# DCDCDC-R2.net
KiCad netlist of a schematic drawn in EAGLE
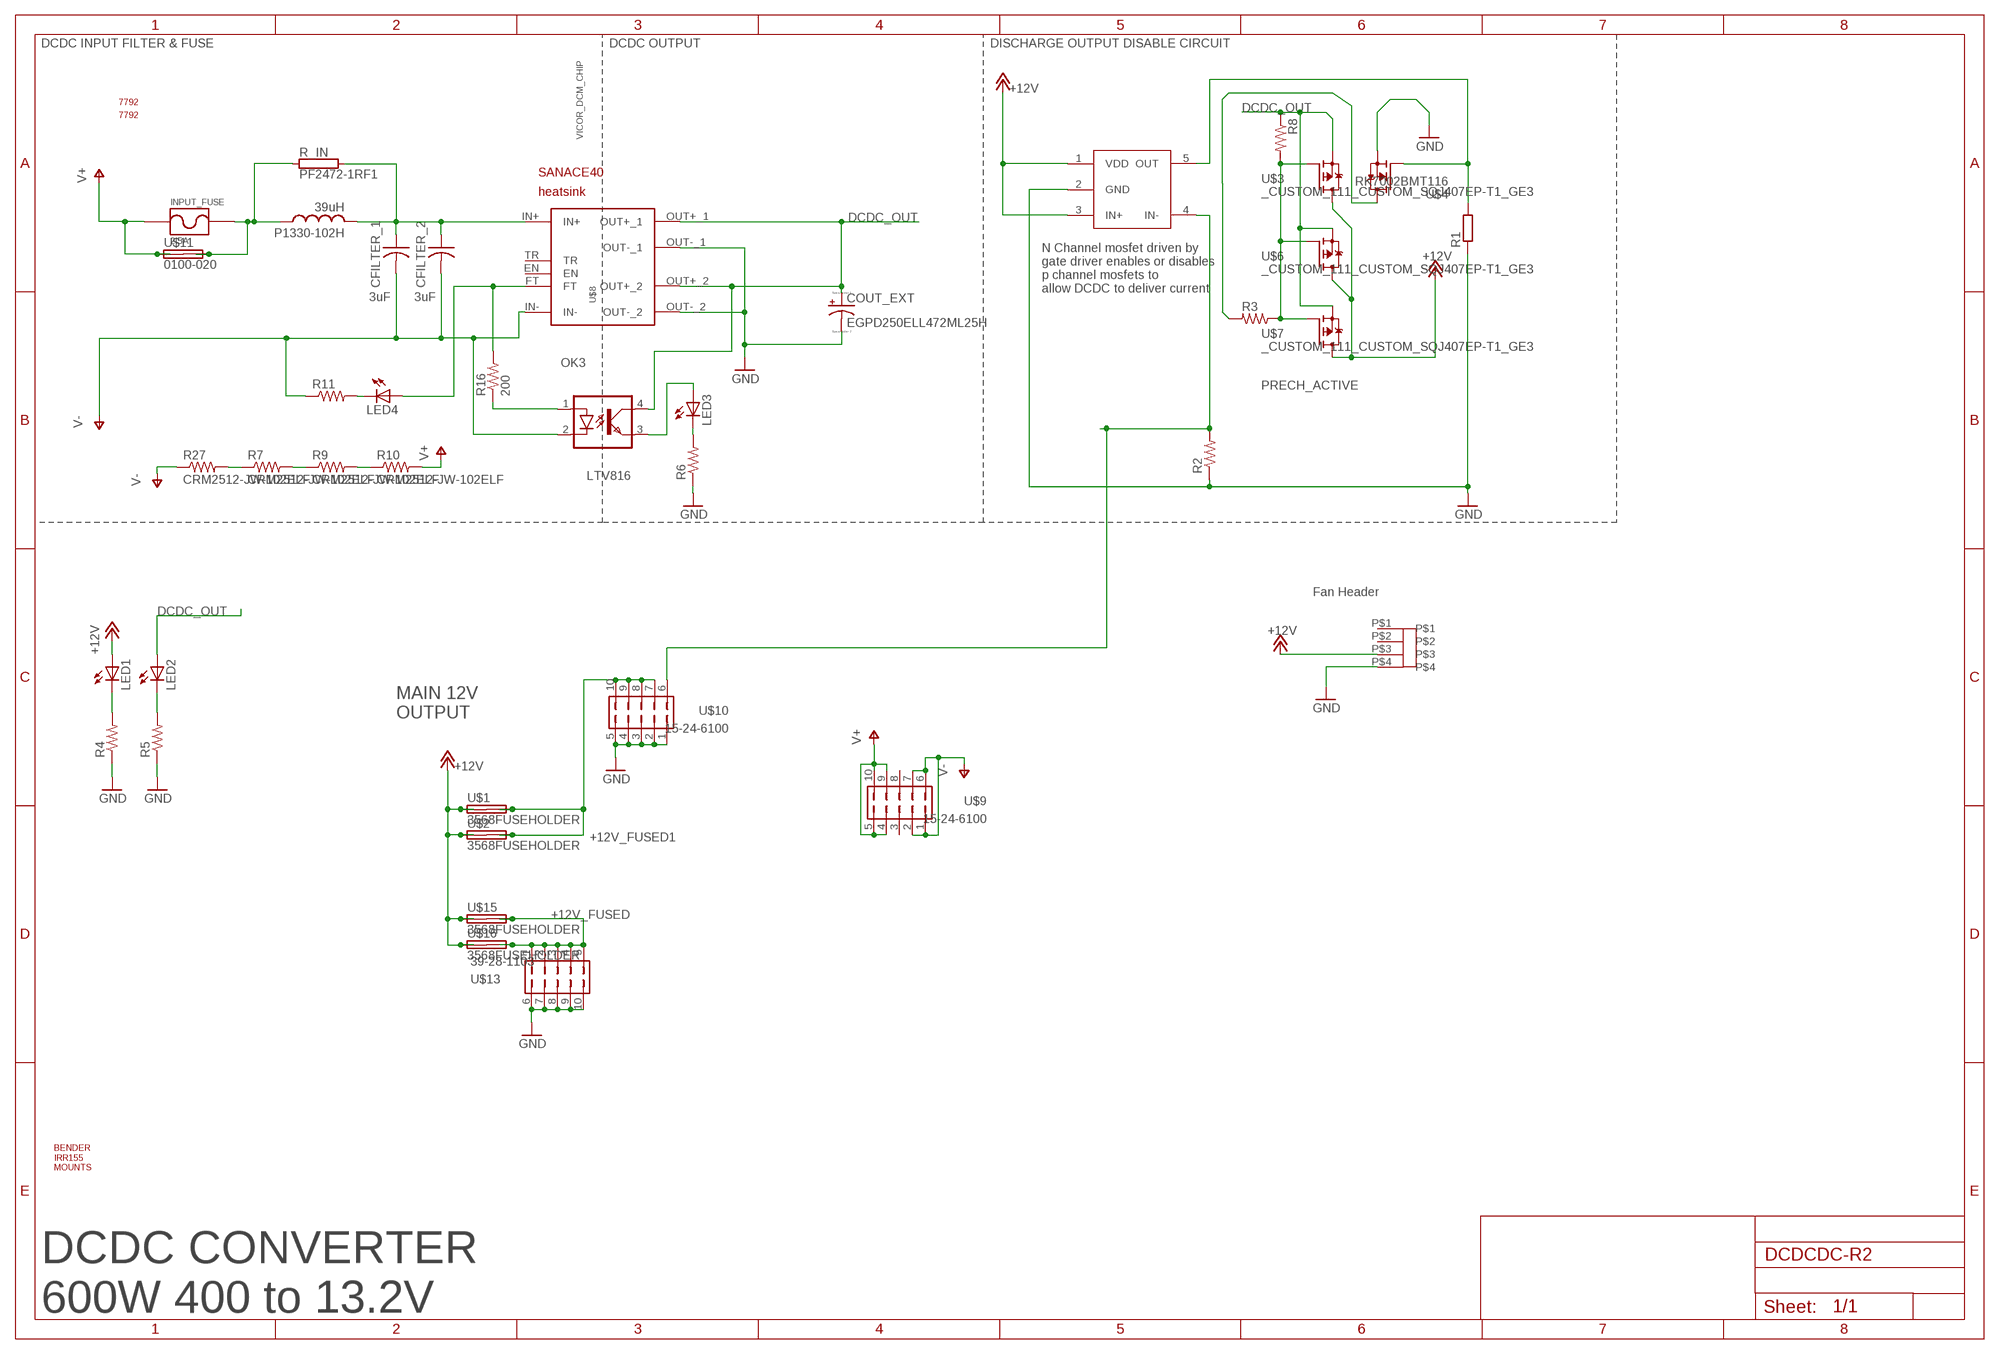
[diagram p0: schematic, sheet 1]

(export (version "E")
  (design (tool "Eeschema 10.0.6"))
  (components
    (comp (ref "CFILTER_1")
      (value "3uF")
      (footprint "eagle-import:CERALINK_FA3")
      (libsource (lib "eagle-import") (part "B58035U5305M062"))
    )
    (comp (ref "CFILTER_2")
      (value "3uF")
      (footprint "eagle-import:CERALINK_FA3")
      (libsource (lib "eagle-import") (part "B58035U5305M062"))
    )
    (comp (ref "COUT_EXT")
      (value "EGPD250ELL472ML25H")
      (footprint "eagle-import:E7,5-16")
      (libsource (lib "eagle-import") (part "CPOL-USE7.5-16"))
    )
    (comp (ref "INPUT_FUSE")
      (value "2.5A")
      (footprint "eagle-import:_CUSTOM_PARTS_LF_885")
      (libsource (lib "eagle-import") (part "_CUSTOM_PARTS_LF_885"))
    )
    (comp (ref "LED1")
      (value "LEDCHIPLED_0805")
      (footprint "eagle-import:CHIPLED_0805")
      (libsource (lib "eagle-import") (part "LEDCHIPLED_0805"))
    )
    (comp (ref "LED2")
      (value "LEDCHIPLED_0805")
      (footprint "eagle-import:CHIPLED_0805")
      (libsource (lib "eagle-import") (part "LEDCHIPLED_0805"))
    )
    (comp (ref "LED3")
      (value "LEDCHIPLED_0805")
      (footprint "eagle-import:CHIPLED_0805")
      (libsource (lib "eagle-import") (part "LEDCHIPLED_0805"))
    )
    (comp (ref "LED4")
      (value "LEDCHIPLED_0805")
      (footprint "eagle-import:CHIPLED_0805")
      (libsource (lib "eagle-import") (part "LEDCHIPLED_0805"))
    )
    (comp (ref "OK3")
      (value "LTV816")
      (footprint "eagle-import:DIL04")
      (libsource (lib "eagle-import") (part "LTV816"))
    )
    (comp (ref "P1330-102H")
      (value "39uH")
      (footprint "eagle-import:L_1510_NONSTANDARD")
      (libsource (lib "eagle-import") (part "SRP1770TA-390M"))
    )
    (comp (ref "R1")
      (value "R-EU_R0805")
      (footprint "eagle-import:R0805")
      (libsource (lib "eagle-import") (part "R-EU_R0805"))
    )
    (comp (ref "R2")
      (value "R-US_R0805")
      (footprint "eagle-import:R0805")
      (libsource (lib "eagle-import") (part "ACC-MB-R0_13324935_R-US_R0805"))
    )
    (comp (ref "R3")
      (value "R-US_R0805")
      (footprint "eagle-import:R0805")
      (libsource (lib "eagle-import") (part "ACC-MB-R0_13324935_R-US_R0805"))
    )
    (comp (ref "R4")
      (value "R-US_R0805")
      (footprint "eagle-import:R0805")
      (libsource (lib "eagle-import") (part "R-US_R0805"))
    )
    (comp (ref "R5")
      (value "R-US_R0805")
      (footprint "eagle-import:R0805")
      (libsource (lib "eagle-import") (part "R-US_R0805"))
    )
    (comp (ref "R6")
      (value "R-US_R0805")
      (footprint "eagle-import:R0805")
      (libsource (lib "eagle-import") (part "R-US_R0805"))
    )
    (comp (ref "R7")
      (value "CRM2512-JW-102ELF")
      (footprint "eagle-import:R2512")
      (libsource (lib "eagle-import") (part "R-US_R2512"))
    )
    (comp (ref "R8")
      (value "R-US_R0805")
      (footprint "eagle-import:R0805")
      (libsource (lib "eagle-import") (part "ACC-MB-R0_13324935_R-US_R0805"))
    )
    (comp (ref "R9")
      (value "CRM2512-JW-102ELF")
      (footprint "eagle-import:R2512")
      (libsource (lib "eagle-import") (part "R-US_R2512"))
    )
    (comp (ref "R10")
      (value "CRM2512-JW-102ELF")
      (footprint "eagle-import:R2512")
      (libsource (lib "eagle-import") (part "R-US_R2512"))
    )
    (comp (ref "R11")
      (value "R-US_R0805")
      (footprint "eagle-import:R0805")
      (libsource (lib "eagle-import") (part "R-US_R0805"))
    )
    (comp (ref "R16")
      (value "200")
      (footprint "eagle-import:R2010")
      (libsource (lib "eagle-import") (part "Main_14107900_R-US_R2010"))
    )
    (comp (ref "R27")
      (value "CRM2512-JW-102ELF")
      (footprint "eagle-import:R2512")
      (libsource (lib "eagle-import") (part "R-US_R2512"))
    )
    (comp (ref "R_IN")
      (value "PF2472-1RF1")
      (footprint "eagle-import:TO-247-2V")
      (libsource (lib "eagle-import") (part "RMG100-V"))
    )
    (comp (ref "U$1")
      (value "3568FUSEHOLDER")
      (footprint "eagle-import:3568")
      (libsource (lib "eagle-import") (part "3568FUSEHOLDER"))
    )
    (comp (ref "U$2")
      (value "3568FUSEHOLDER")
      (footprint "eagle-import:3568")
      (libsource (lib "eagle-import") (part "3568FUSEHOLDER"))
    )
    (comp (ref "U$3")
      (value "_CUSTOM_111_CUSTOM_SQJ407EP-T1_GE3")
      (footprint "eagle-import:_CUSTOM_111_CUSTOM_TRANS_SIRA90DP-T1-GE3")
      (libsource (lib "eagle-import") (part "_CUSTOM_111_CUSTOM_SQJ407EP-T1_GE3"))
    )
    (comp (ref "U$4")
      (value "RK7002BMT116")
      (footprint "eagle-import:SOT23")
      (libsource (lib "eagle-import") (part "RK7002BMT116"))
    )
    (comp (ref "U$5")
      (value "UCC27511AQDBVRQ1")
      (footprint "eagle-import:SOT23-5L")
      (libsource (lib "eagle-import") (part "UCC27511AQDBVRQ1"))
    )
    (comp (ref "U$6")
      (value "_CUSTOM_111_CUSTOM_SQJ407EP-T1_GE3")
      (footprint "eagle-import:_CUSTOM_111_CUSTOM_TRANS_SIRA90DP-T1-GE3")
      (libsource (lib "eagle-import") (part "_CUSTOM_111_CUSTOM_SQJ407EP-T1_GE3"))
    )
    (comp (ref "U$7")
      (value "_CUSTOM_111_CUSTOM_SQJ407EP-T1_GE3")
      (footprint "eagle-import:_CUSTOM_111_CUSTOM_TRANS_SIRA90DP-T1-GE3")
      (libsource (lib "eagle-import") (part "_CUSTOM_111_CUSTOM_SQJ407EP-T1_GE3"))
    )
    (comp (ref "U$8")
      (value "VICOR_DCM_CHIP")
      (footprint "eagle-import:VICOR_CHIP_HEATSINK")
      (libsource (lib "eagle-import") (part "VICOR_DCM_CHIP"))
    )
    (comp (ref "U$9")
      (value "15-24-6100")
      (footprint "eagle-import:15-24-6100")
      (libsource (lib "eagle-import") (part "15-24-6100"))
    )
    (comp (ref "U$10")
      (value "15-24-6100")
      (footprint "eagle-import:15-24-6100")
      (libsource (lib "eagle-import") (part "15-24-6100"))
    )
    (comp (ref "U$11")
      (value "0100-020")
      (footprint "eagle-import:0100-020")
      (libsource (lib "eagle-import") (part "0100-020"))
    )
    (comp (ref "U$12")
      (value "VICOR_HEATSINK_DOUBLE")
      (footprint "eagle-import:VICOR_HEATSINK_DOUBLE")
      (libsource (lib "eagle-import") (part "VICOR_HEATSINK_DOUBLE"))
    )
    (comp (ref "U$13")
      (value "39-28-1103")
      (footprint "eagle-import:39-28-1103")
      (libsource (lib "eagle-import") (part "39-28-1103"))
    )
    (comp (ref "U$14")
      (value "7792")
      (footprint "eagle-import:7792")
      (libsource (lib "eagle-import") (part "7792"))
    )
    (comp (ref "U$15")
      (value "3568FUSEHOLDER")
      (footprint "eagle-import:3568")
      (libsource (lib "eagle-import") (part "3568FUSEHOLDER"))
    )
    (comp (ref "U$16")
      (value "3568FUSEHOLDER")
      (footprint "eagle-import:3568")
      (libsource (lib "eagle-import") (part "3568FUSEHOLDER"))
    )
    (comp (ref "U$17")
      (value "7792")
      (footprint "eagle-import:7792")
      (libsource (lib "eagle-import") (part "7792"))
    )
    (comp (ref "U$18")
      (value "9GAX0412P3S0031")
      (footprint "eagle-import:SANACE40")
      (libsource (lib "eagle-import") (part "SANACE40"))
    )
    (comp (ref "U$19")
      (value "470531000")
      (footprint "eagle-import:470531000")
      (libsource (lib "eagle-import") (part "470531000"))
    )
    (comp (ref "U$20")
      (value "BENDER_IRR155")
      (footprint "eagle-import:BENDER_IRR155")
      (libsource (lib "eagle-import") (part "BENDER_IRR155"))
    )
  )
  (nets
    (net (code "1") (name "+12V") (class "Default")
      (node (ref "LED1") (pin "A") (pinfunction "A_A") (pintype "passive"))
      (node (ref "U$1") (pin "L1") (pinfunction "1A_L1") (pintype "passive"))
      (node (ref "U$1") (pin "L2") (pinfunction "1B_L2") (pintype "passive"))
      (node (ref "U$15") (pin "L1") (pinfunction "1A_L1") (pintype "passive"))
      (node (ref "U$15") (pin "L2") (pinfunction "1B_L2") (pintype "passive"))
      (node (ref "U$16") (pin "L1") (pinfunction "1A_L1") (pintype "passive"))
      (node (ref "U$16") (pin "L2") (pinfunction "1B_L2") (pintype "passive"))
      (node (ref "U$19") (pin "P$3") (pinfunction "P$3_P$3") (pintype "bidirectional"))
      (node (ref "U$2") (pin "L1") (pinfunction "1A_L1") (pintype "passive"))
      (node (ref "U$2") (pin "L2") (pinfunction "1B_L2") (pintype "passive"))
      (node (ref "U$3") (pin "5") (pinfunction "D_5") (pintype "passive"))
      (node (ref "U$5") (pin "1") (pinfunction "VDD_1") (pintype "bidirectional"))
      (node (ref "U$5") (pin "3") (pinfunction "IN+_3") (pintype "bidirectional"))
      (node (ref "U$6") (pin "5") (pinfunction "D_5") (pintype "passive"))
      (node (ref "U$7") (pin "5") (pinfunction "D_5") (pintype "passive"))
    )
    (net (code "2") (name "/+12V_FUSED") (class "Default")
      (node (ref "U$13") (pin "1") (pinfunction "1_1") (pintype "passive"))
      (node (ref "U$13") (pin "2") (pinfunction "2_2") (pintype "passive"))
      (node (ref "U$13") (pin "3") (pinfunction "3_3") (pintype "passive"))
      (node (ref "U$13") (pin "4") (pinfunction "4_4") (pintype "passive"))
      (node (ref "U$13") (pin "5") (pinfunction "5_5") (pintype "passive"))
      (node (ref "U$15") (pin "R1") (pinfunction "2A_R1") (pintype "passive"))
      (node (ref "U$15") (pin "R2") (pinfunction "2B_R2") (pintype "passive"))
      (node (ref "U$16") (pin "R1") (pinfunction "2A_R1") (pintype "passive"))
      (node (ref "U$16") (pin "R2") (pinfunction "2B_R2") (pintype "passive"))
    )
    (net (code "3") (name "/+12V_FUSED1") (class "Default")
      (node (ref "U$1") (pin "R1") (pinfunction "2A_R1") (pintype "passive"))
      (node (ref "U$1") (pin "R2") (pinfunction "2B_R2") (pintype "passive"))
      (node (ref "U$10") (pin "10") (pinfunction "10_10") (pintype "passive"))
      (node (ref "U$10") (pin "7") (pinfunction "7_7") (pintype "passive"))
      (node (ref "U$10") (pin "8") (pinfunction "8_8") (pintype "passive"))
      (node (ref "U$10") (pin "9") (pinfunction "9_9") (pintype "passive"))
      (node (ref "U$2") (pin "R1") (pinfunction "2A_R1") (pintype "passive"))
      (node (ref "U$2") (pin "R2") (pinfunction "2B_R2") (pintype "passive"))
    )
    (net (code "4") (name "/DCDC_OUT") (class "Default")
      (node (ref "COUT_EXT") (pin "+") (pinfunction "+_+") (pintype "passive"))
      (node (ref "LED2") (pin "A") (pinfunction "A_A") (pintype "passive"))
      (node (ref "OK3") (pin "4") (pinfunction "COL_4") (pintype "passive"))
      (node (ref "R8") (pin "1") (pinfunction "1_1") (pintype "passive"))
      (node (ref "U$3") (pin "1") (pinfunction "S_1") (pintype "passive"))
      (node (ref "U$3") (pin "2") (pinfunction "S_2") (pintype "passive"))
      (node (ref "U$3") (pin "3") (pinfunction "S_3") (pintype "passive"))
      (node (ref "U$6") (pin "1") (pinfunction "S_1") (pintype "passive"))
      (node (ref "U$6") (pin "2") (pinfunction "S_2") (pintype "passive"))
      (node (ref "U$6") (pin "3") (pinfunction "S_3") (pintype "passive"))
      (node (ref "U$7") (pin "1") (pinfunction "S_1") (pintype "passive"))
      (node (ref "U$7") (pin "2") (pinfunction "S_2") (pintype "passive"))
      (node (ref "U$7") (pin "3") (pinfunction "S_3") (pintype "passive"))
      (node (ref "U$8") (pin "OUT+_1") (pinfunction "OUT+_1_OUT+_1") (pintype "bidirectional"))
      (node (ref "U$8") (pin "OUT+_2") (pinfunction "OUT+_2_OUT+_2") (pintype "bidirectional"))
    )
    (net (code "5") (name "/PRECH_ACTIVE") (class "Default")
      (node (ref "R2") (pin "2") (pinfunction "2_2") (pintype "passive"))
      (node (ref "U$10") (pin "6") (pinfunction "6_6") (pintype "passive"))
      (node (ref "U$5") (pin "4") (pinfunction "IN-_4") (pintype "bidirectional"))
    )
    (net (code "6") (name "GND") (class "Default")
      (node (ref "COUT_EXT") (pin "-") (pinfunction "-_-") (pintype "passive"))
      (node (ref "R1") (pin "1") (pinfunction "1_1") (pintype "passive"))
      (node (ref "R2") (pin "1") (pinfunction "1_1") (pintype "passive"))
      (node (ref "R4") (pin "1") (pinfunction "1_1") (pintype "passive"))
      (node (ref "R5") (pin "1") (pinfunction "1_1") (pintype "passive"))
      (node (ref "R6") (pin "1") (pinfunction "1_1") (pintype "passive"))
      (node (ref "U$10") (pin "1") (pinfunction "1_1") (pintype "passive"))
      (node (ref "U$10") (pin "2") (pinfunction "2_2") (pintype "passive"))
      (node (ref "U$10") (pin "3") (pinfunction "3_3") (pintype "passive"))
      (node (ref "U$10") (pin "4") (pinfunction "4_4") (pintype "passive"))
      (node (ref "U$10") (pin "5") (pinfunction "5_5") (pintype "passive"))
      (node (ref "U$13") (pin "10") (pinfunction "10_10") (pintype "passive"))
      (node (ref "U$13") (pin "6") (pinfunction "6_6") (pintype "passive"))
      (node (ref "U$13") (pin "7") (pinfunction "7_7") (pintype "passive"))
      (node (ref "U$13") (pin "8") (pinfunction "8_8") (pintype "passive"))
      (node (ref "U$13") (pin "9") (pinfunction "9_9") (pintype "passive"))
      (node (ref "U$19") (pin "P$4") (pinfunction "P$4_P$4") (pintype "bidirectional"))
      (node (ref "U$4") (pin "2") (pinfunction "S_2") (pintype "passive"))
      (node (ref "U$5") (pin "2") (pinfunction "GND_2") (pintype "bidirectional"))
      (node (ref "U$8") (pin "OUT-_1") (pinfunction "OUT-_1_OUT-_1") (pintype "bidirectional"))
      (node (ref "U$8") (pin "OUT-_2") (pinfunction "OUT-_2_OUT-_2") (pintype "bidirectional"))
    )
    (net (code "7") (name "Net-(CFILTER_1-1)") (class "Default")
      (node (ref "CFILTER_1") (pin "P$1") (pinfunction "1_P$1") (pintype "passive"))
      (node (ref "CFILTER_2") (pin "P$1") (pinfunction "1_P$1") (pintype "passive"))
      (node (ref "P1330-102H") (pin "P$2") (pinfunction "2_P$2") (pintype "passive"))
      (node (ref "R_IN") (pin "2") (pinfunction "2_2") (pintype "passive"))
      (node (ref "U$8") (pin "IN+") (pinfunction "IN+_IN+") (pintype "bidirectional"))
    )
    (net (code "8") (name "Net-(LED1-PadC)") (class "Default")
      (node (ref "LED1") (pin "C") (pinfunction "C_C") (pintype "passive"))
      (node (ref "R4") (pin "2") (pinfunction "2_2") (pintype "passive"))
    )
    (net (code "9") (name "Net-(LED2-PadC)") (class "Default")
      (node (ref "LED2") (pin "C") (pinfunction "C_C") (pintype "passive"))
      (node (ref "R5") (pin "2") (pinfunction "2_2") (pintype "passive"))
    )
    (net (code "10") (name "Net-(LED3-PadC)") (class "Default")
      (node (ref "LED3") (pin "C") (pinfunction "C_C") (pintype "passive"))
      (node (ref "R6") (pin "2") (pinfunction "2_2") (pintype "passive"))
    )
    (net (code "11") (name "Net-(LED4-PadA)") (class "Default")
      (node (ref "LED4") (pin "A") (pinfunction "A_A") (pintype "passive"))
      (node (ref "R16") (pin "2") (pinfunction "2_2") (pintype "passive"))
      (node (ref "U$8") (pin "FT") (pinfunction "FT_FT") (pintype "bidirectional"))
    )
    (net (code "12") (name "Net-(LED4-PadC)") (class "Default")
      (node (ref "LED4") (pin "C") (pinfunction "C_C") (pintype "passive"))
      (node (ref "R11") (pin "2") (pinfunction "2_2") (pintype "passive"))
    )
    (net (code "13") (name "Net-(OK3-A)") (class "Default")
      (node (ref "OK3") (pin "1") (pinfunction "A_1") (pintype "passive"))
      (node (ref "R16") (pin "1") (pinfunction "1_1") (pintype "passive"))
    )
    (net (code "14") (name "Net-(OK3-EMIT)") (class "Default")
      (node (ref "LED3") (pin "A") (pinfunction "A_A") (pintype "passive"))
      (node (ref "OK3") (pin "3") (pinfunction "EMIT_3") (pintype "passive"))
    )
    (net (code "15") (name "Net-(P1330-102H-1)") (class "Default")
      (node (ref "INPUT_FUSE") (pin "P$2") (pinfunction "P$2_P$2") (pintype "bidirectional"))
      (node (ref "P1330-102H") (pin "P$1") (pinfunction "1_P$1") (pintype "passive"))
      (node (ref "R_IN") (pin "1") (pinfunction "1_1") (pintype "passive"))
      (node (ref "U$11") (pin "P$2") (pinfunction "2A_P$2") (pintype "passive"))
      (node (ref "U$11") (pin "P$4") (pinfunction "2B_P$4") (pintype "passive"))
    )
    (net (code "16") (name "Net-(R7-Pad2)") (class "Default")
      (node (ref "R7") (pin "2") (pinfunction "2_2") (pintype "passive"))
      (node (ref "R9") (pin "1") (pinfunction "1_1") (pintype "passive"))
    )
    (net (code "17") (name "Net-(R10-Pad1)") (class "Default")
      (node (ref "R10") (pin "1") (pinfunction "1_1") (pintype "passive"))
      (node (ref "R9") (pin "2") (pinfunction "2_2") (pintype "passive"))
    )
    (net (code "18") (name "Net-(R27-Pad2)") (class "Default")
      (node (ref "R27") (pin "2") (pinfunction "2_2") (pintype "passive"))
      (node (ref "R7") (pin "1") (pinfunction "1_1") (pintype "passive"))
    )
    (net (code "19") (name "Net-(U$3-G)") (class "Default")
      (node (ref "R3") (pin "1") (pinfunction "1_1") (pintype "passive"))
      (node (ref "R8") (pin "2") (pinfunction "2_2") (pintype "passive"))
      (node (ref "U$3") (pin "4") (pinfunction "G_4") (pintype "passive"))
      (node (ref "U$6") (pin "4") (pinfunction "G_4") (pintype "passive"))
      (node (ref "U$7") (pin "4") (pinfunction "G_4") (pintype "passive"))
    )
    (net (code "20") (name "Net-(U$4-D)") (class "Default")
      (node (ref "R3") (pin "2") (pinfunction "2_2") (pintype "passive"))
      (node (ref "U$4") (pin "3") (pinfunction "D_3") (pintype "passive"))
    )
    (net (code "21") (name "Net-(U$4-G)") (class "Default")
      (node (ref "R1") (pin "2") (pinfunction "2_2") (pintype "passive"))
      (node (ref "U$4") (pin "1") (pinfunction "G_1") (pintype "passive"))
      (node (ref "U$5") (pin "5") (pinfunction "OUT_5") (pintype "bidirectional"))
    )
    (net (code "22") (name "V+") (class "Default")
      (node (ref "INPUT_FUSE") (pin "P$1") (pinfunction "P$1_P$1") (pintype "bidirectional"))
      (node (ref "R10") (pin "2") (pinfunction "2_2") (pintype "passive"))
      (node (ref "U$11") (pin "P$1") (pinfunction "1A_P$1") (pintype "passive"))
      (node (ref "U$11") (pin "P$3") (pinfunction "1B_P$3") (pintype "passive"))
      (node (ref "U$9") (pin "10") (pinfunction "10_10") (pintype "passive"))
      (node (ref "U$9") (pin "4") (pinfunction "4_4") (pintype "passive"))
      (node (ref "U$9") (pin "5") (pinfunction "5_5") (pintype "passive"))
      (node (ref "U$9") (pin "9") (pinfunction "9_9") (pintype "passive"))
    )
    (net (code "23") (name "V-") (class "Default")
      (node (ref "CFILTER_1") (pin "P$2") (pinfunction "2_P$2") (pintype "passive"))
      (node (ref "CFILTER_2") (pin "P$2") (pinfunction "2_P$2") (pintype "passive"))
      (node (ref "OK3") (pin "2") (pinfunction "C_2") (pintype "passive"))
      (node (ref "R11") (pin "1") (pinfunction "1_1") (pintype "passive"))
      (node (ref "R27") (pin "1") (pinfunction "1_1") (pintype "passive"))
      (node (ref "U$8") (pin "IN-") (pinfunction "IN-_IN-") (pintype "bidirectional"))
      (node (ref "U$9") (pin "1") (pinfunction "1_1") (pintype "passive"))
      (node (ref "U$9") (pin "2") (pinfunction "2_2") (pintype "passive"))
      (node (ref "U$9") (pin "6") (pinfunction "6_6") (pintype "passive"))
      (node (ref "U$9") (pin "7") (pinfunction "7_7") (pintype "passive"))
    )
    (net (code "24") (name "unconnected-(U$8-PadEN)") (class "Default")
      (node (ref "U$8") (pin "EN") (pinfunction "EN_EN") (pintype "bidirectional"))
    )
    (net (code "25") (name "unconnected-(U$8-PadTR)") (class "Default")
      (node (ref "U$8") (pin "TR") (pinfunction "TR_TR") (pintype "bidirectional"))
    )
    (net (code "26") (name "unconnected-(U$9-Pad3)") (class "Default")
      (node (ref "U$9") (pin "3") (pinfunction "3_3") (pintype "passive"))
    )
    (net (code "27") (name "unconnected-(U$9-Pad8)") (class "Default")
      (node (ref "U$9") (pin "8") (pinfunction "8_8") (pintype "passive"))
    )
    (net (code "28") (name "unconnected-(U$19-PadP$1)") (class "Default")
      (node (ref "U$19") (pin "P$1") (pinfunction "P$1_P$1") (pintype "bidirectional"))
    )
    (net (code "29") (name "unconnected-(U$19-PadP$2)") (class "Default")
      (node (ref "U$19") (pin "P$2") (pinfunction "P$2_P$2") (pintype "bidirectional"))
    )
  )
)
